# Indicators.net
KiCad netlist of a schematic drawn in Altium Designer
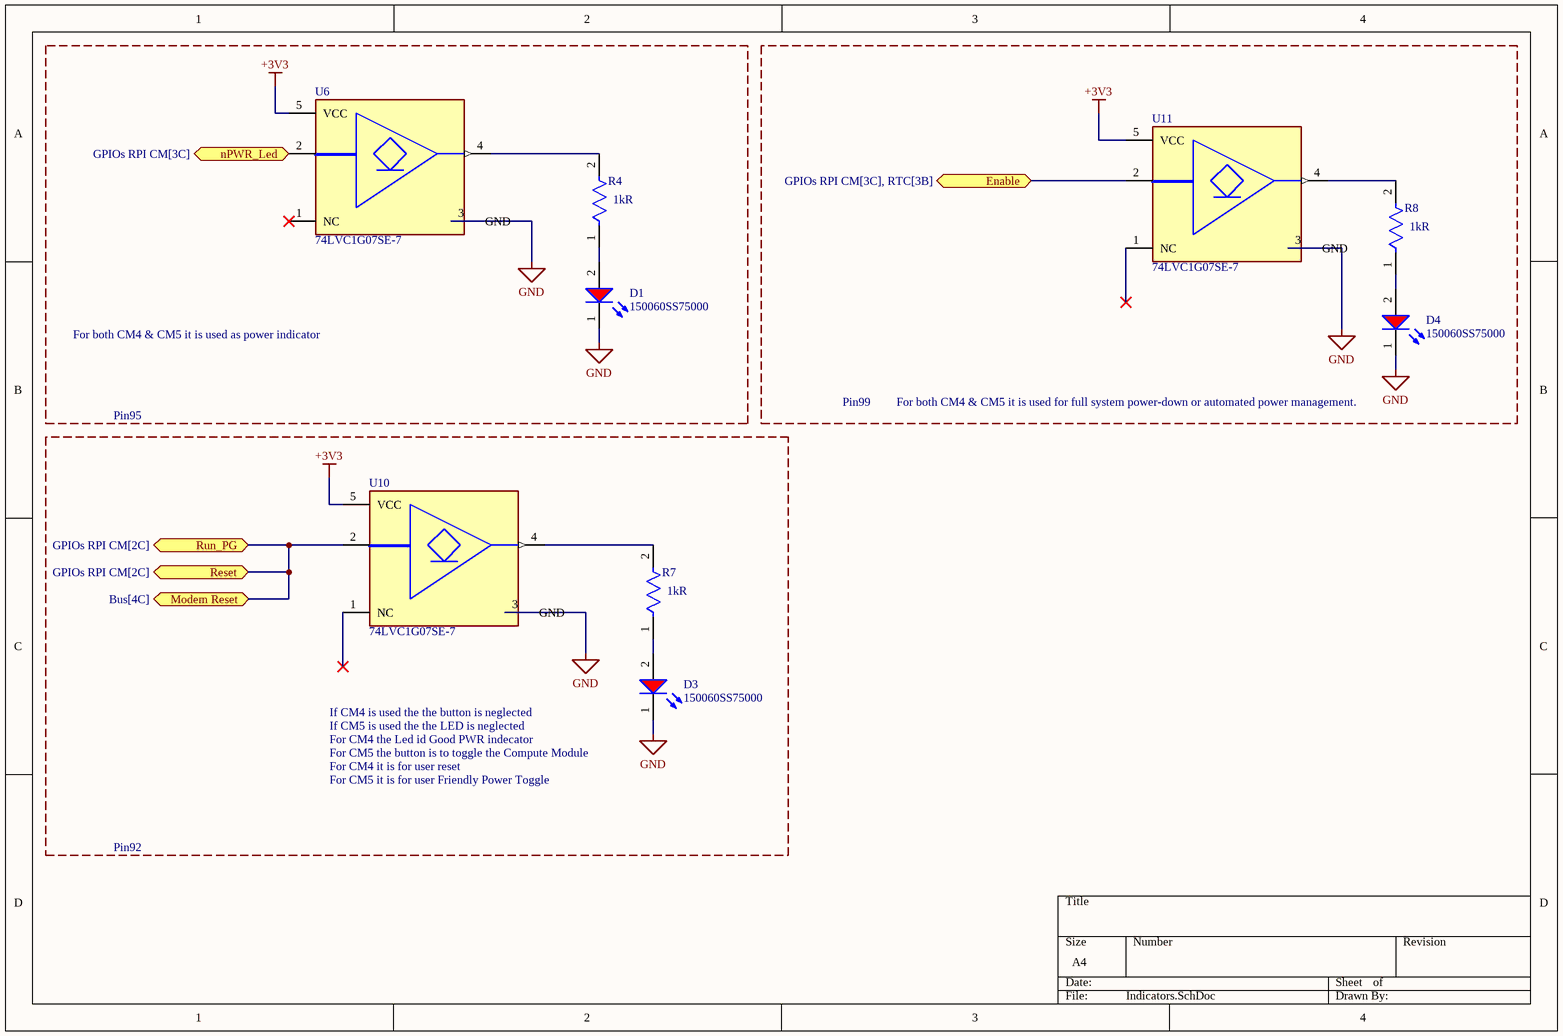
[diagram p0: Indicators.SchDoc]

(export (version "E")
  (design (tool "Eeschema 10.0.6"))
  (components
    (comp (ref "D1")
      (value "150060SS75000")
      (footprint "WL-SMCW_0603_150060xx75000")
      (description "Led, Red, 630 Nm, 1.9 V, 30 Ma, 60 Mcd Rohs Compliant: Yes")
      (libsource (lib "Altium Content Vault") (part "LED_Red_2A-1K"))
    )
    (comp (ref "D3")
      (value "150060SS75000")
      (footprint "WL-SMCW_0603_150060xx75000")
      (description "Led, Red, 630 Nm, 1.9 V, 30 Ma, 60 Mcd Rohs Compliant: Yes")
      (libsource (lib "Altium Content Vault") (part "LED_Red_2A-1K"))
    )
    (comp (ref "D4")
      (value "150060SS75000")
      (footprint "WL-SMCW_0603_150060xx75000")
      (description "Led, Red, 630 Nm, 1.9 V, 30 Ma, 60 Mcd Rohs Compliant: Yes")
      (libsource (lib "Altium Content Vault") (part "LED_Red_2A-1K"))
    )
    (comp (ref "R4")
      (value "ERA-3AEB102V")
      (footprint "FP-ERA3A-IPC_C")
      (description "RES SMD 1K OHM 0.1% 1/10W 0603")
      (fields (field (name "TOLERANCE") "0.1%") (field (name "RESISTANCE") "1kR"))
      (libsource (lib "Altium Content Vault") (part "1029c3af85768c4190bb7ad29bc67b5"))
    )
    (comp (ref "R7")
      (value "ERA-3AEB102V")
      (footprint "FP-ERA3A-IPC_C")
      (description "RES SMD 1K OHM 0.1% 1/10W 0603")
      (fields (field (name "TOLERANCE") "0.1%") (field (name "RESISTANCE") "1kR"))
      (libsource (lib "Altium Content Vault") (part "1029c3af85768c4190bb7ad29bc67b5"))
    )
    (comp (ref "R8")
      (value "ERA-3AEB102V")
      (footprint "FP-ERA3A-IPC_C")
      (description "RES SMD 1K OHM 0.1% 1/10W 0603")
      (fields (field (name "TOLERANCE") "0.1%") (field (name "RESISTANCE") "1kR"))
      (libsource (lib "Altium Content Vault") (part "1029c3af85768c4190bb7ad29bc67b5"))
    )
    (comp (ref "U6")
      (value "74LVC1G07SE-7")
      (footprint "FP-SOT353-MFG")
      (description "IC BUF NON-INVERT 5.5V SOT353")
      (fields
        (field (name "MANUFACTURER") "Diodes Inc.")
        (field (name "OCTOPART") "https://octopart.com/74lvc1g07se-7-diodes+inc.-18882698")
      )
      (libsource (lib "Altium Content Vault") (part "1af1fa4339a335f25e71eb4dc151592"))
    )
    (comp (ref "U10")
      (value "74LVC1G07SE-7")
      (footprint "FP-SOT353-MFG")
      (description "IC BUF NON-INVERT 5.5V SOT353")
      (fields
        (field (name "MANUFACTURER") "Diodes Inc.")
        (field (name "OCTOPART") "https://octopart.com/74lvc1g07se-7-diodes+inc.-18882698")
      )
      (libsource (lib "Altium Content Vault") (part "1af1fa4339a335f25e71eb4dc151592"))
    )
    (comp (ref "U11")
      (value "74LVC1G07SE-7")
      (footprint "FP-SOT353-MFG")
      (description "IC BUF NON-INVERT 5.5V SOT353")
      (fields
        (field (name "MANUFACTURER") "Diodes Inc.")
        (field (name "OCTOPART") "https://octopart.com/74lvc1g07se-7-diodes+inc.-18882698")
      )
      (libsource (lib "Altium Content Vault") (part "1af1fa4339a335f25e71eb4dc151592"))
    )
  )
  (nets
    (net (code "1") (name "+3V3") (class "Default")
      (node (ref "U10") (pin "5") (pinfunction "VCC_5") (pintype "power_in"))
      (node (ref "U11") (pin "5") (pinfunction "VCC_5") (pintype "power_in"))
      (node (ref "U6") (pin "5") (pinfunction "VCC_5") (pintype "power_in"))
    )
    (net (code "2") (name "/Enable") (class "Default")
      (node (ref "U11") (pin "2") (pinfunction "A_2") (pintype "passive"))
    )
    (net (code "3") (name "/Modem Reset") (class "Default")
      (node (ref "U10") (pin "2") (pinfunction "A_2") (pintype "passive"))
    )
    (net (code "4") (name "/nPWR_Led") (class "Default")
      (node (ref "U6") (pin "2") (pinfunction "A_2") (pintype "passive"))
    )
    (net (code "5") (name "GND") (class "Default")
      (node (ref "D1") (pin "1") (pinfunction "K_1") (pintype "passive"))
      (node (ref "D3") (pin "1") (pinfunction "K_1") (pintype "passive"))
      (node (ref "D4") (pin "1") (pinfunction "K_1") (pintype "passive"))
      (node (ref "U10") (pin "3") (pinfunction "GND_3") (pintype "power_in"))
      (node (ref "U11") (pin "3") (pinfunction "GND_3") (pintype "power_in"))
      (node (ref "U6") (pin "3") (pinfunction "GND_3") (pintype "power_in"))
    )
    (net (code "6") (name "Net-(D1-A)") (class "Default")
      (node (ref "D1") (pin "2") (pinfunction "A_2") (pintype "passive"))
      (node (ref "R4") (pin "1") (pinfunction "1_1") (pintype "passive"))
    )
    (net (code "7") (name "Net-(D3-A)") (class "Default")
      (node (ref "D3") (pin "2") (pinfunction "A_2") (pintype "passive"))
      (node (ref "R7") (pin "1") (pinfunction "1_1") (pintype "passive"))
    )
    (net (code "8") (name "Net-(D4-A)") (class "Default")
      (node (ref "D4") (pin "2") (pinfunction "A_2") (pintype "passive"))
      (node (ref "R8") (pin "1") (pinfunction "1_1") (pintype "passive"))
    )
    (net (code "9") (name "Net-(U6-Y)") (class "Default")
      (node (ref "R4") (pin "2") (pinfunction "2_2") (pintype "passive"))
      (node (ref "U6") (pin "4") (pinfunction "Y_4") (pintype "output"))
    )
    (net (code "10") (name "Net-(U10-Y)") (class "Default")
      (node (ref "R7") (pin "2") (pinfunction "2_2") (pintype "passive"))
      (node (ref "U10") (pin "4") (pinfunction "Y_4") (pintype "output"))
    )
    (net (code "11") (name "Net-(U11-Y)") (class "Default")
      (node (ref "R8") (pin "2") (pinfunction "2_2") (pintype "passive"))
      (node (ref "U11") (pin "4") (pinfunction "Y_4") (pintype "output"))
    )
    (net (code "12") (name "unconnected-(U6-NC-Pad1)") (class "Default")
      (node (ref "U6") (pin "1") (pinfunction "NC_1") (pintype "passive+no_connect"))
    )
    (net (code "13") (name "unconnected-(U10-NC-Pad1)") (class "Default")
      (node (ref "U10") (pin "1") (pinfunction "NC_1") (pintype "passive+no_connect"))
    )
    (net (code "14") (name "unconnected-(U11-NC-Pad1)") (class "Default")
      (node (ref "U11") (pin "1") (pinfunction "NC_1") (pintype "passive+no_connect"))
    )
  )
)
